# Inertial_Measurement_RTC.net
KiCad netlist of a schematic drawn in Altium Designer
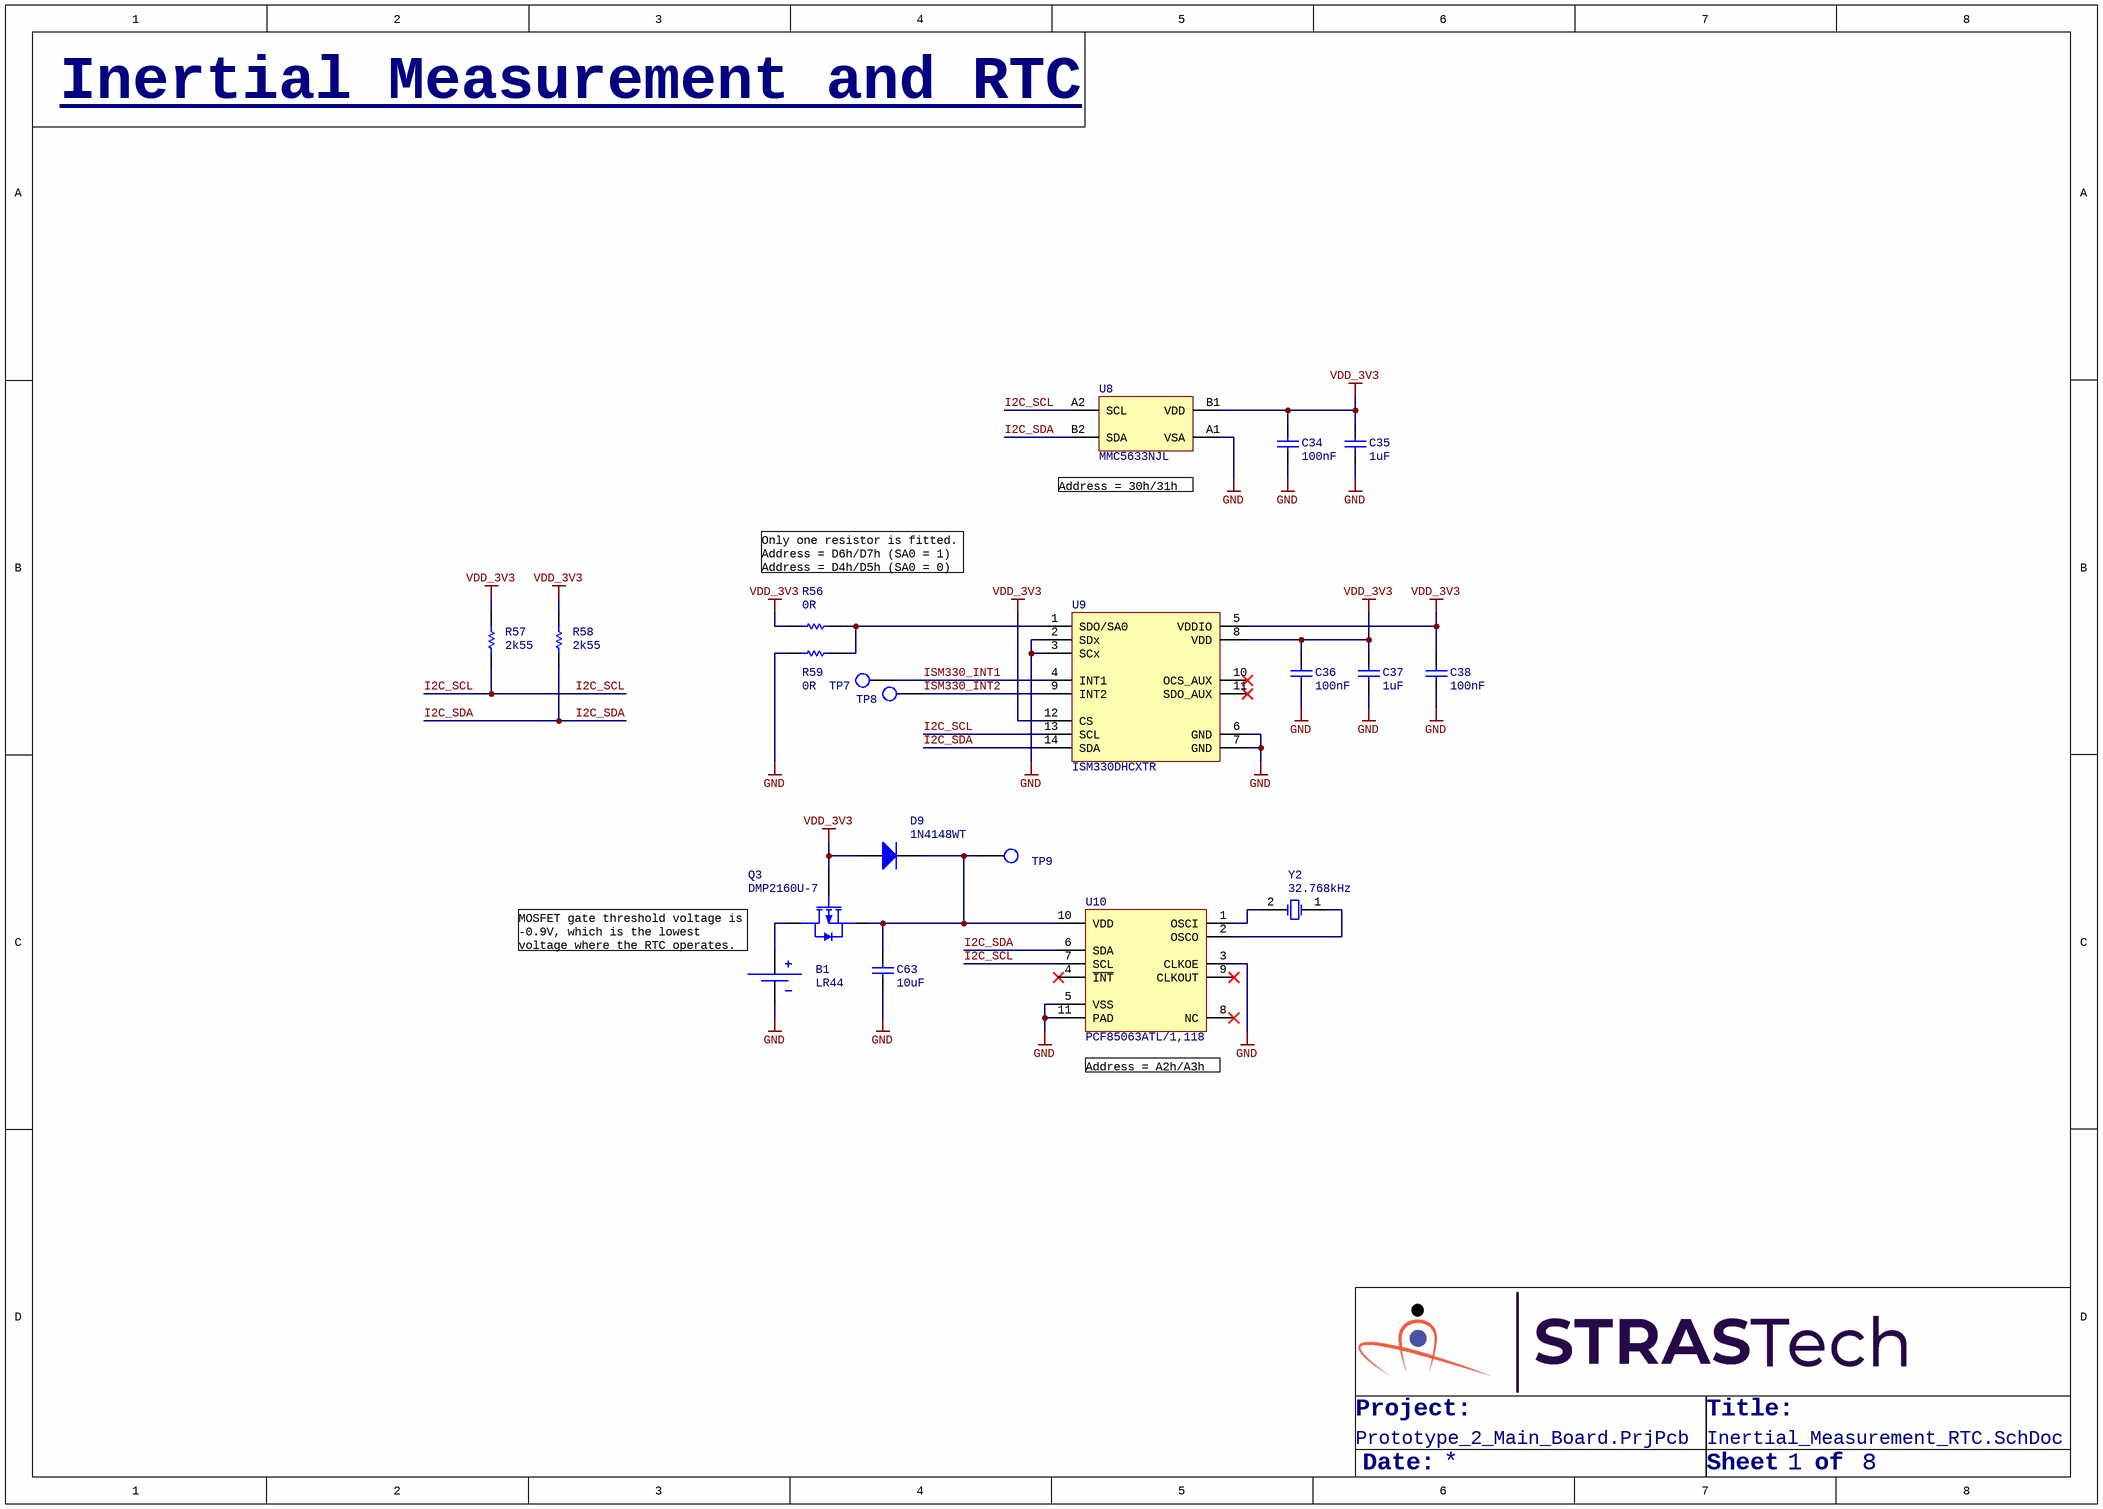
[diagram p0: Inertial_Measurement_RTC.SchDoc]

(export (version "E")
  (design (tool "Eeschema 10.0.6"))
  (components
    (comp (ref "B1")
      (value "LR44")
      (footprint "Holder,Cell,LR44,PCB,Thru")
      (description "Battery Retainer Coin, 11.6mm 1 Cell PC Pin")
      (fields
        (field (name "MANUFACTURER") "Keystone Electronics")
        (field (name "MANUFACTURER PART NUMBER") "2997")
        (field (name "CREATEDBY") "Judd Foster")
      )
      (libsource (lib "symbols") (part "Holder,Cell,LR44,PCB,Thru"))
    )
    (comp (ref "C34")
      (value "100nF")
      (footprint "Cap,SMD,0402")
      (description "0.1µF ±10% 25V Ceramic Capacitor X7R 0402 (1005 Metric)")
      (fields
        (field (name "VENDOR PART NUMBER") "490-14603-1-ND")
        (field (name "MANUFACTURER") "Murata Electronics")
        (field (name "CREATEDBY") "Judd Foster")
      )
      (libsource (lib "symbols") (part "CAP,Cer,100nF,25VDC,X7R,0402"))
    )
    (comp (ref "C35")
      (value "1uF")
      (footprint "Cap,SMD,0402")
      (description "1 µF ±10% 35V Ceramic Capacitor X5R 0402 (1005 Metric)")
      (fields
        (field (name "VENDOR PART NUMBER") "445-9073-1-ND")
        (field (name "MANUFACTURER") "TDK Corporation")
        (field (name "CREATEDBY") "Judd Foster")
      )
      (libsource (lib "symbols") (part "CAP,Cer,1uF,35VDC,X5R,0402"))
    )
    (comp (ref "C36")
      (value "100nF")
      (footprint "Cap,SMD,0402")
      (description "0.1µF ±10% 25V Ceramic Capacitor X7R 0402 (1005 Metric)")
      (fields
        (field (name "VENDOR PART NUMBER") "490-14603-1-ND")
        (field (name "MANUFACTURER") "Murata Electronics")
        (field (name "CREATEDBY") "Judd Foster")
      )
      (libsource (lib "symbols") (part "CAP,Cer,100nF,25VDC,X7R,0402"))
    )
    (comp (ref "C37")
      (value "1uF")
      (footprint "Cap,SMD,0402")
      (description "1 µF ±10% 35V Ceramic Capacitor X5R 0402 (1005 Metric)")
      (fields
        (field (name "VENDOR PART NUMBER") "445-9073-1-ND")
        (field (name "MANUFACTURER") "TDK Corporation")
        (field (name "CREATEDBY") "Judd Foster")
      )
      (libsource (lib "symbols") (part "CAP,Cer,1uF,35VDC,X5R,0402"))
    )
    (comp (ref "C38")
      (value "100nF")
      (footprint "Cap,SMD,0402")
      (description "0.1µF ±10% 25V Ceramic Capacitor X7R 0402 (1005 Metric)")
      (fields
        (field (name "VENDOR PART NUMBER") "490-14603-1-ND")
        (field (name "MANUFACTURER") "Murata Electronics")
        (field (name "CREATEDBY") "Judd Foster")
      )
      (libsource (lib "symbols") (part "CAP,Cer,100nF,25VDC,X7R,0402"))
    )
    (comp (ref "C63")
      (value "10uF")
      (footprint "Cap,SMD,0402")
      (description "10 µF ±20% 10V Ceramic Capacitor X5R 0402 (1005 Metric)")
      (fields
        (field (name "VENDOR PART NUMBER") "1276-1450-1-ND")
        (field (name "MANUFACTURER") "Samsung Electro-Mechanics")
        (field (name "CREATEDBY") "Judd Foster")
      )
      (libsource (lib "symbols") (part "CAP,Cer,10uF,10VDC,X5R,0402"))
    )
    (comp (ref "D9")
      (value "1N4148WT")
      (footprint "SOD523")
      (description "Diode Standard 75 V 200mA Surface Mount SOD-523F")
      (fields
        (field (name "MANUFACTURER") "ON Semiconductor")
        (field (name "VENDOR PART NUMBER") "1N4148WTCT-ND")
        (field (name "CREATEDBY") "Judd Foster")
      )
      (libsource (lib "symbols") (part "DIODE,Gen,75V,200mA,SOD523F"))
    )
    (comp (ref "Q3")
      (value "DMP2160U-7")
      (footprint "SOT23-3")
      (description "P-Channel 20 V 3.2A (Ta) 1.4W (Ta) Surface Mount SOT-23-3")
      (fields
        (field (name "MANUFACTURER") "Diodes Incorporated")
        (field (name "VENDOR PART NUMBER") "DMP2160UDICT-ND")
        (field (name "CREATEDBY") "Judd Foster")
      )
      (libsource (lib "symbols") (part "MOSFET,P Ch,20V,3.2A"))
    )
    (comp (ref "R56")
      (value "0R")
      (footprint "RES,0402")
      (description "0 Ohms Jumper 0.1W, 1/10W Chip Resistor 0402 (1005 Metric) Automotive AEC-Q200 Thick Film")
      (fields
        (field (name "MANUFACTURER") "Panasonic Electronic Components")
        (field (name "MANUFACTURER PART NUMBER") "ERJ-2GE0R00X")
        (field (name "CREATEDBY") "Judd Foster")
      )
      (libsource (lib "symbols") (part "RES,0R0,0.1W,0402"))
    )
    (comp (ref "R57")
      (value "2k55")
      (footprint "RES,0402")
      (description "2.55 kOhms ±1% 0.063W, 1/16W Chip Resistor 0402 (1005 Metric) Automotive AEC-Q200 Thick Film")
      (fields
        (field (name "MANUFACTURER") "Stackpole Electronics Inc")
        (field (name "MANUFACTURER PART NUMBER") "RMCF0402FT2K55")
        (field (name "CREATEDBY") "Judd Foster")
      )
      (libsource (lib "symbols") (part "RES,2k55,1%,0.063W,0402"))
    )
    (comp (ref "R58")
      (value "2k55")
      (footprint "RES,0402")
      (description "2.55 kOhms ±1% 0.063W, 1/16W Chip Resistor 0402 (1005 Metric) Automotive AEC-Q200 Thick Film")
      (fields
        (field (name "MANUFACTURER") "Stackpole Electronics Inc")
        (field (name "MANUFACTURER PART NUMBER") "RMCF0402FT2K55")
        (field (name "CREATEDBY") "Judd Foster")
      )
      (libsource (lib "symbols") (part "RES,2k55,1%,0.063W,0402"))
    )
    (comp (ref "R59")
      (value "0R")
      (footprint "RES,0402")
      (description "0 Ohms Jumper 0.1W, 1/10W Chip Resistor 0402 (1005 Metric) Automotive AEC-Q200 Thick Film")
      (fields
        (field (name "MANUFACTURER") "Panasonic Electronic Components")
        (field (name "MANUFACTURER PART NUMBER") "ERJ-2GE0R00X")
        (field (name "CREATEDBY") "Judd Foster")
      )
      (libsource (lib "symbols") (part "RES,0R0,0.1W,0402"))
    )
    (comp (ref "TP7")
      (value "TESTPOINT")
      (footprint "testpoint,smd,round,1mm")
      (description "PCB Testpoint")
      (fields (field (name "CREATEDBY") "Judd Foster"))
      (libsource (lib "symbols") (part "TESTPOINT"))
    )
    (comp (ref "TP8")
      (value "TESTPOINT")
      (footprint "testpoint,smd,round,1mm")
      (description "PCB Testpoint")
      (fields (field (name "CREATEDBY") "Judd Foster"))
      (libsource (lib "symbols") (part "TESTPOINT"))
    )
    (comp (ref "TP9")
      (value "TESTPOINT")
      (footprint "testpoint,smd,round,1mm")
      (description "PCB Testpoint")
      (fields (field (name "CREATEDBY") "Judd Foster"))
      (libsource (lib "symbols") (part "TESTPOINT"))
    )
    (comp (ref "U8")
      (value "MMC5633NJL")
      (footprint "IC,WLP,2x2,P0.4mm")
      (description "Magnetoresistive Sensor X, Y, Z Axis 4-WLP (0.85x0.85)")
      (fields
        (field (name "MANUFACTURER") "Memsic Inc.")
        (field (name "VENDOR PART NUMBER") "1267-MMC5633NJLCT-ND")
        (field (name "CREATEDBY") "Judd Foster")
      )
      (libsource (lib "symbols") (part "MMC5633NJL"))
    )
    (comp (ref "U9")
      (value "ISM330DHCXTR")
      (footprint "IC,LGA-14L,2.5x3mm")
      (description "Accelerometer, Gyroscope, Temperature, 6 Axis Sensor I²C, SPI Output")
      (fields
        (field (name "MANUFACTURER") "STMicroelectronics")
        (field (name "VENDOR PART NUMBER") "497-19784-1-ND")
        (field (name "CREATEDBY") "Judd Foster")
      )
      (libsource (lib "symbols") (part "ISM330DHCXTR"))
    )
    (comp (ref "U10")
      (value "PCF85063ATL/1,118")
      (footprint "IC,DFN-10_3x3,P0.5mm")
      (description "Real Time Clock (RTC) IC Clock/Calendar - I²C, 2-Wire Serial 10-XFDFN Exposed Pad")
      (fields
        (field (name "MANUFACTURER") "NXP USA Inc.")
        (field (name "VENDOR PART NUMBER") "568-10235-1-ND")
        (field (name "CREATEDBY") "Judd Foster")
      )
      (libsource (lib "symbols") (part "PCF85063ATL/1,118"))
    )
    (comp (ref "Y2")
      (value "32.768kHz")
      (footprint "XTAL,SMD,2PIN,2.0x1.2MM")
      (description "32.768 kHz ±20ppm Crystal 9pF 70 kOhms 2-SMD, No Lead")
      (fields
        (field (name "MANUFACTURER") "Micro Crystal AG")
        (field (name "MANUFACTURER PART NUMBER") "CM8V-T1A-32.768KHZ-9PF-20PPM-TA-QC")
        (field (name "CREATEDBY") "Judd Foster")
      )
      (libsource (lib "symbols") (part "XTAL,32.768kHz,9pF,SMD"))
    )
  )
  (nets
    (net (code "1") (name "/I2C_SCL") (class "Default")
      (node (ref "R57") (pin "1") (pinfunction "1_1") (pintype "passive"))
      (node (ref "U10") (pin "7") (pinfunction "SCL_7") (pintype "passive"))
      (node (ref "U8") (pin "A2") (pinfunction "SCL_A2") (pintype "passive"))
      (node (ref "U9") (pin "13") (pinfunction "SCL_13") (pintype "passive"))
    )
    (net (code "2") (name "/I2C_SDA") (class "Default")
      (node (ref "R58") (pin "1") (pinfunction "1_1") (pintype "passive"))
      (node (ref "U10") (pin "6") (pinfunction "SDA_6") (pintype "passive"))
      (node (ref "U8") (pin "B2") (pinfunction "SDA_B2") (pintype "passive"))
      (node (ref "U9") (pin "14") (pinfunction "SDA_14") (pintype "passive"))
    )
    (net (code "3") (name "/ISM330_INT1") (class "Default")
      (node (ref "TP7") (pin "1") (pinfunction "TP_1") (pintype "passive"))
      (node (ref "U9") (pin "4") (pinfunction "INT1_4") (pintype "passive"))
    )
    (net (code "4") (name "/ISM330_INT2") (class "Default")
      (node (ref "TP8") (pin "1") (pinfunction "TP_1") (pintype "passive"))
      (node (ref "U9") (pin "9") (pinfunction "INT2_9") (pintype "passive"))
    )
    (net (code "5") (name "GND") (class "Default")
      (node (ref "B1") (pin "2") (pinfunction "BATT_N_2") (pintype "passive"))
      (node (ref "C34") (pin "2") (pinfunction "2_2") (pintype "passive"))
      (node (ref "C35") (pin "1") (pinfunction "1_1") (pintype "passive"))
      (node (ref "C36") (pin "1") (pinfunction "1_1") (pintype "passive"))
      (node (ref "C37") (pin "1") (pinfunction "1_1") (pintype "passive"))
      (node (ref "C38") (pin "1") (pinfunction "1_1") (pintype "passive"))
      (node (ref "C63") (pin "2") (pinfunction "2_2") (pintype "passive"))
      (node (ref "R59") (pin "1") (pinfunction "1_1") (pintype "passive"))
      (node (ref "U10") (pin "11") (pinfunction "PAD_11") (pintype "passive"))
      (node (ref "U10") (pin "3") (pinfunction "CLKOE_3") (pintype "passive"))
      (node (ref "U10") (pin "5") (pinfunction "VSS_5") (pintype "passive"))
      (node (ref "U8") (pin "A1") (pinfunction "VSA_A1") (pintype "passive"))
      (node (ref "U9") (pin "2") (pinfunction "SDx_2") (pintype "passive"))
      (node (ref "U9") (pin "3") (pinfunction "SCx_3") (pintype "passive"))
      (node (ref "U9") (pin "6") (pinfunction "GND_6") (pintype "passive"))
      (node (ref "U9") (pin "7") (pinfunction "GND_7") (pintype "passive"))
    )
    (net (code "6") (name "Net-(B1-BATT_P)") (class "Default")
      (node (ref "B1") (pin "1") (pinfunction "BATT_P_1") (pintype "passive"))
      (node (ref "Q3") (pin "3") (pinfunction "D_3") (pintype "passive"))
    )
    (net (code "7") (name "Net-(D9-K)") (class "Default")
      (node (ref "C63") (pin "1") (pinfunction "1_1") (pintype "passive"))
      (node (ref "D9") (pin "1") (pinfunction "K_1") (pintype "passive"))
      (node (ref "Q3") (pin "2") (pinfunction "S_2") (pintype "passive"))
      (node (ref "TP9") (pin "1") (pinfunction "TP_1") (pintype "passive"))
      (node (ref "U10") (pin "10") (pinfunction "VDD_10") (pintype "passive"))
    )
    (net (code "8") (name "Net-(U9-SDO{slash}SA0)") (class "Default")
      (node (ref "R56") (pin "2") (pinfunction "2_2") (pintype "passive"))
      (node (ref "R59") (pin "2") (pinfunction "2_2") (pintype "passive"))
      (node (ref "U9") (pin "1") (pinfunction "SDO/SA0_1") (pintype "passive"))
    )
    (net (code "9") (name "Net-(U10-OSCI)") (class "Default")
      (node (ref "U10") (pin "1") (pinfunction "OSCI_1") (pintype "passive"))
      (node (ref "Y2") (pin "2") (pinfunction "GND_2") (pintype "passive"))
    )
    (net (code "10") (name "Net-(U10-OSCO)") (class "Default")
      (node (ref "U10") (pin "2") (pinfunction "OSCO_2") (pintype "passive"))
      (node (ref "Y2") (pin "1") (pinfunction "OSC1_1") (pintype "passive"))
    )
    (net (code "11") (name "VDD_3V3") (class "Default")
      (node (ref "C34") (pin "1") (pinfunction "1_1") (pintype "passive"))
      (node (ref "C35") (pin "2") (pinfunction "2_2") (pintype "passive"))
      (node (ref "C36") (pin "2") (pinfunction "2_2") (pintype "passive"))
      (node (ref "C37") (pin "2") (pinfunction "2_2") (pintype "passive"))
      (node (ref "C38") (pin "2") (pinfunction "2_2") (pintype "passive"))
      (node (ref "D9") (pin "2") (pinfunction "A_2") (pintype "passive"))
      (node (ref "Q3") (pin "1") (pinfunction "G_1") (pintype "passive"))
      (node (ref "R56") (pin "1") (pinfunction "1_1") (pintype "passive"))
      (node (ref "R57") (pin "2") (pinfunction "2_2") (pintype "passive"))
      (node (ref "R58") (pin "2") (pinfunction "2_2") (pintype "passive"))
      (node (ref "U8") (pin "B1") (pinfunction "VDD_B1") (pintype "passive"))
      (node (ref "U9") (pin "12") (pinfunction "CS_12") (pintype "passive"))
      (node (ref "U9") (pin "5") (pinfunction "VDDIO_5") (pintype "passive"))
      (node (ref "U9") (pin "8") (pinfunction "VDD_8") (pintype "passive"))
    )
    (net (code "12") (name "unconnected-(U9-OCS_AUX-Pad10)") (class "Default")
      (node (ref "U9") (pin "10") (pinfunction "OCS_AUX_10") (pintype "passive+no_connect"))
    )
    (net (code "13") (name "unconnected-(U9-SDO_AUX-Pad11)") (class "Default")
      (node (ref "U9") (pin "11") (pinfunction "SDO_AUX_11") (pintype "passive+no_connect"))
    )
    (net (code "14") (name "unconnected-(U10-CLKOUT-Pad9)") (class "Default")
      (node (ref "U10") (pin "9") (pinfunction "CLKOUT_9") (pintype "passive+no_connect"))
    )
    (net (code "15") (name "unconnected-(U10-NC-Pad8)") (class "Default")
      (node (ref "U10") (pin "8") (pinfunction "NC_8") (pintype "passive+no_connect"))
    )
    (net (code "16") (name "unconnected-(U10-~{INT}-Pad4)") (class "Default")
      (node (ref "U10") (pin "4") (pinfunction "~{INT}_4") (pintype "passive+no_connect"))
    )
  )
)
